# projekt.net
KiCad netlist of a schematic drawn in EAGLE
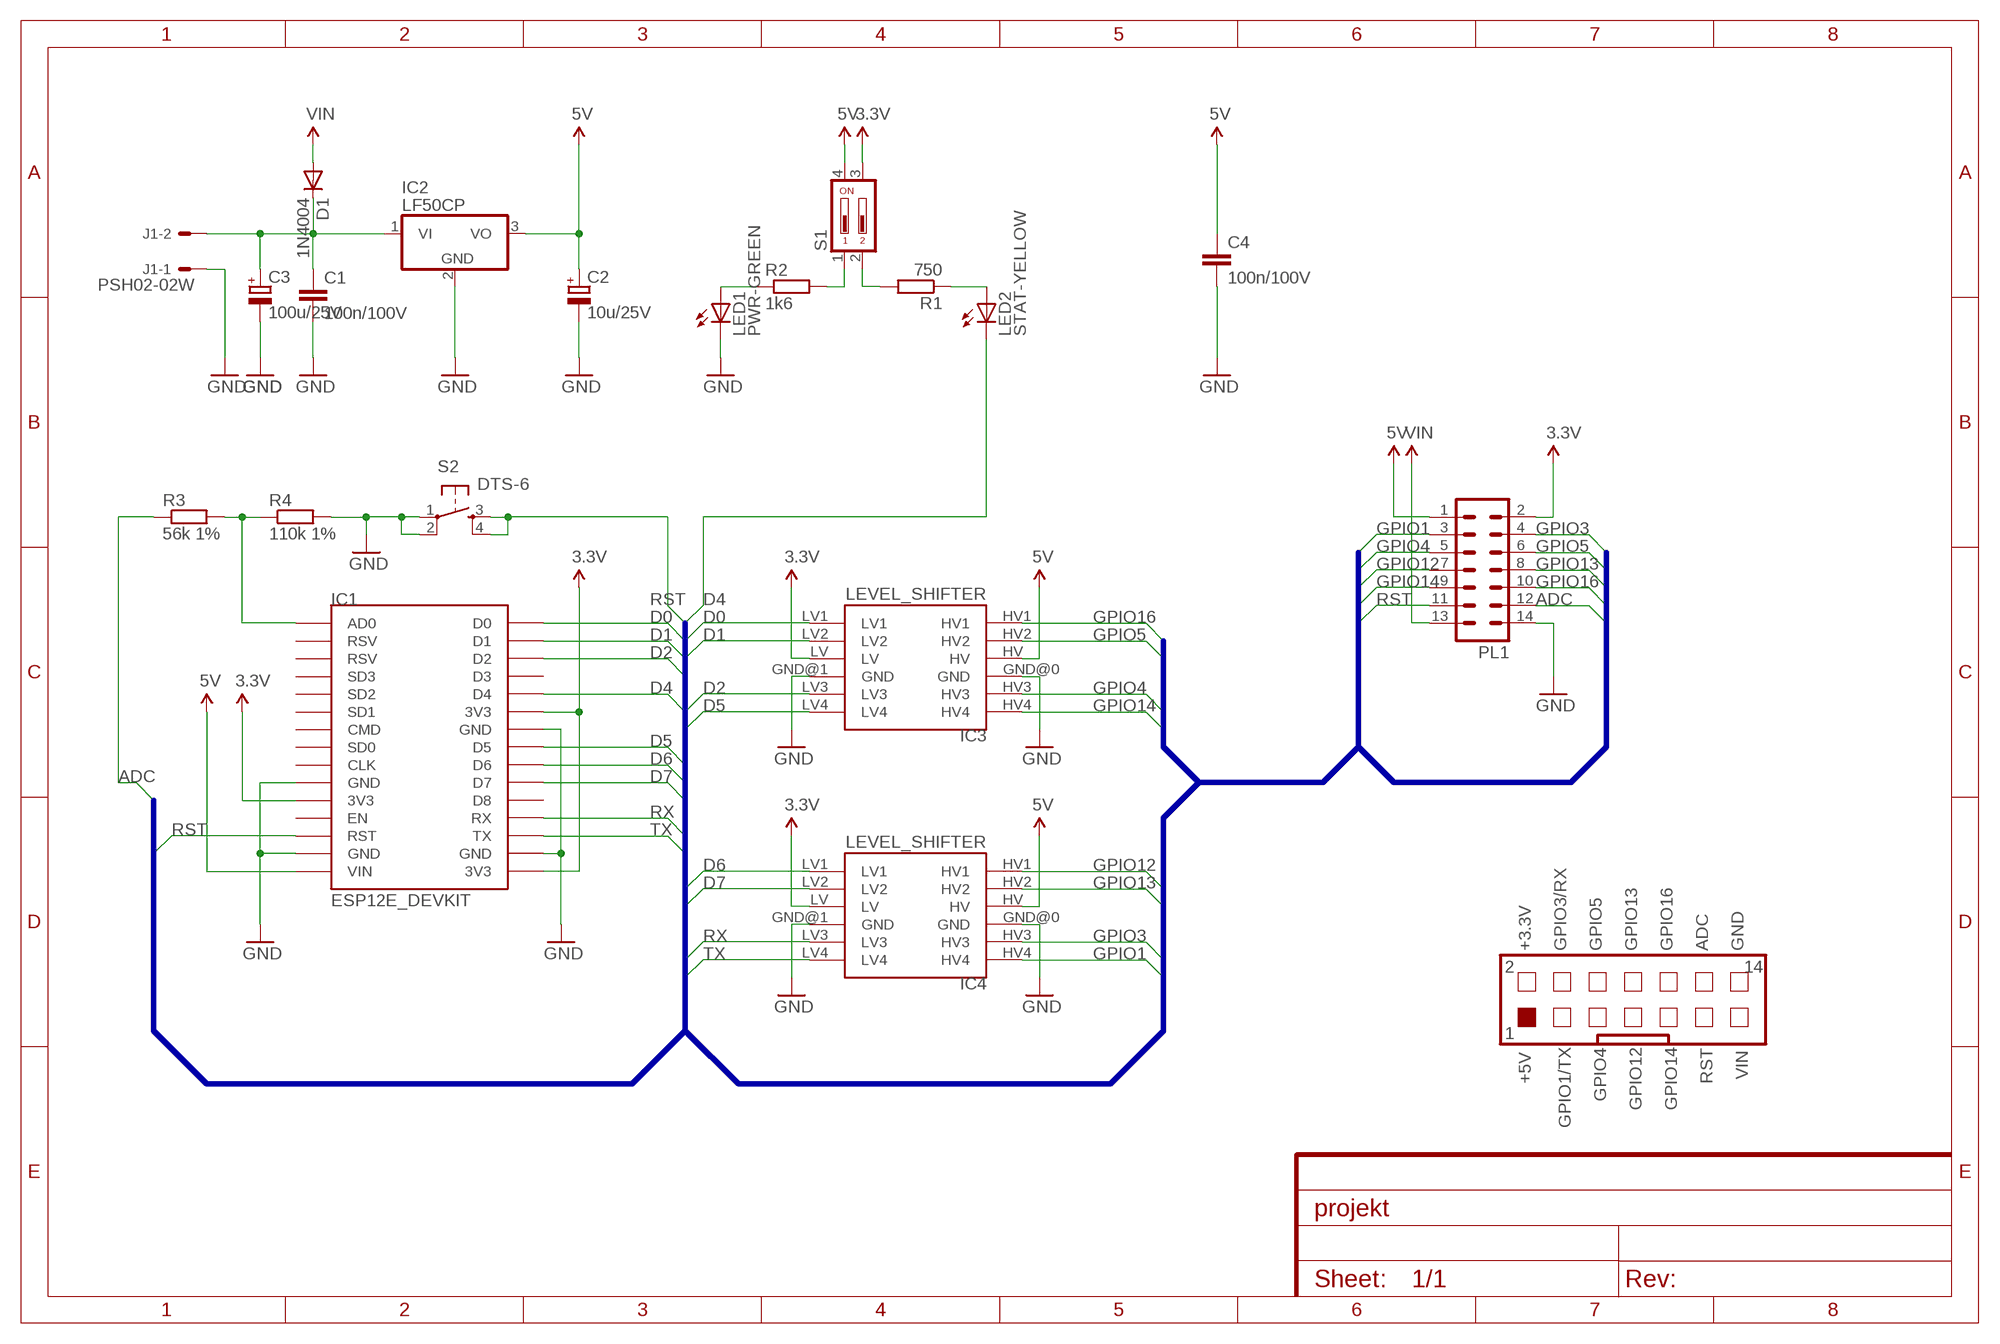
[diagram p0: schematic, sheet 1]

(export (version "E")
  (design (tool "Eeschema 10.0.6"))
  (components
    (comp (ref "C1")
      (value "100n/100V")
      (footprint "eagle-import:C025-025X050")
      (libsource (lib "eagle-import") (part "C-EUC025-025X050"))
    )
    (comp (ref "C2")
      (value "10u/25V")
      (footprint "eagle-import:E3,5-8")
      (libsource (lib "eagle-import") (part "CPOL-EUE3,5-8"))
    )
    (comp (ref "C3")
      (value "100u/25V")
      (footprint "eagle-import:E5-13")
      (libsource (lib "eagle-import") (part "CPOL-EUE5-13"))
    )
    (comp (ref "C4")
      (value "100n/100V")
      (footprint "eagle-import:C025-025X050")
      (libsource (lib "eagle-import") (part "C-EUC025-025X050"))
    )
    (comp (ref "D1")
      (value "1N4004")
      (footprint "eagle-import:DO41-10")
      (libsource (lib "eagle-import") (part "1N4004"))
    )
    (comp (ref "IC1")
      (value "ESP12E_DEVKIT")
      (footprint "eagle-import:ESP12E_DEVKIT")
      (libsource (lib "eagle-import") (part "ESP12E_DEVKIT"))
    )
    (comp (ref "IC2")
      (value "LF50CP")
      (footprint "eagle-import:TO220H")
      (libsource (lib "eagle-import") (part "LF50CP"))
    )
    (comp (ref "IC3")
      (value "LEVEL_SHIFTER")
      (footprint "eagle-import:LEVEL_SHIFTER")
      (libsource (lib "eagle-import") (part "LEVEL_SHIFTER"))
    )
    (comp (ref "IC4")
      (value "LEVEL_SHIFTER")
      (footprint "eagle-import:LEVEL_SHIFTER")
      (libsource (lib "eagle-import") (part "LEVEL_SHIFTER"))
    )
    (comp (ref "J1")
      (value "PSH02-02W")
      (footprint "eagle-import:7395-02")
      (libsource (lib "eagle-import") (part "22-?-0205-7028"))
    )
    (comp (ref "LED1")
      (value "PWR-GREEN")
      (footprint "eagle-import:LED3MM")
      (libsource (lib "eagle-import") (part "LED3MM"))
    )
    (comp (ref "LED2")
      (value "STAT-YELLOW")
      (footprint "eagle-import:LED3MM")
      (libsource (lib "eagle-import") (part "LED3MM"))
    )
    (comp (ref "PL1")
      (value "14H")
      (footprint "eagle-import:14H")
      (libsource (lib "eagle-import") (part "14H"))
    )
    (comp (ref "R1")
      (value "750")
      (footprint "eagle-import:R1206")
      (libsource (lib "eagle-import") (part "R-EU_R1206"))
    )
    (comp (ref "R2")
      (value "1k6")
      (footprint "eagle-import:R1206")
      (libsource (lib "eagle-import") (part "R-EU_R1206"))
    )
    (comp (ref "R3")
      (value "56k 1%")
      (footprint "eagle-import:R1206")
      (libsource (lib "eagle-import") (part "R-EU_R1206"))
    )
    (comp (ref "R4")
      (value "110k 1%")
      (footprint "eagle-import:R1206")
      (libsource (lib "eagle-import") (part "R-EU_R1206"))
    )
    (comp (ref "S1")
      (value "DIP02YL")
      (footprint "eagle-import:DIP02YL")
      (libsource (lib "eagle-import") (part "DIP02YL"))
    )
    (comp (ref "S2")
      (value "DTS-6")
      (footprint "eagle-import:DTS-6")
      (libsource (lib "eagle-import") (part "DTS-6"))
    )
  )
  (nets
    (net (code "1") (name "/ADC") (class "Default")
      (node (ref "PL1") (pin "12") (pinfunction "12_12") (pintype "passive"))
      (node (ref "R3") (pin "1") (pinfunction "1_1") (pintype "passive"))
    )
    (net (code "2") (name "/D0") (class "Default")
      (node (ref "IC1") (pin "D0") (pinfunction "D0_D0") (pintype "bidirectional"))
      (node (ref "IC3") (pin "LV1") (pinfunction "LV1_LV1") (pintype "bidirectional"))
    )
    (net (code "3") (name "/D1") (class "Default")
      (node (ref "IC1") (pin "D1") (pinfunction "D1_D1") (pintype "bidirectional"))
      (node (ref "IC3") (pin "LV2") (pinfunction "LV2_LV2") (pintype "bidirectional"))
    )
    (net (code "4") (name "/D2") (class "Default")
      (node (ref "IC1") (pin "D2") (pinfunction "D2_D2") (pintype "bidirectional"))
      (node (ref "IC3") (pin "LV3") (pinfunction "LV3_LV3") (pintype "bidirectional"))
    )
    (net (code "5") (name "/D4") (class "Default")
      (node (ref "IC1") (pin "D4") (pinfunction "D4_D4") (pintype "bidirectional"))
      (node (ref "LED2") (pin "K") (pinfunction "C_K") (pintype "passive"))
    )
    (net (code "6") (name "/D5") (class "Default")
      (node (ref "IC1") (pin "D5") (pinfunction "D5_D5") (pintype "bidirectional"))
      (node (ref "IC3") (pin "LV4") (pinfunction "LV4_LV4") (pintype "bidirectional"))
    )
    (net (code "7") (name "/D6") (class "Default")
      (node (ref "IC1") (pin "D6") (pinfunction "D6_D6") (pintype "bidirectional"))
      (node (ref "IC4") (pin "LV1") (pinfunction "LV1_LV1") (pintype "bidirectional"))
    )
    (net (code "8") (name "/D7") (class "Default")
      (node (ref "IC1") (pin "D7") (pinfunction "D7_D7") (pintype "bidirectional"))
      (node (ref "IC4") (pin "LV2") (pinfunction "LV2_LV2") (pintype "bidirectional"))
    )
    (net (code "9") (name "/GPIO1") (class "Default")
      (node (ref "IC4") (pin "HV4") (pinfunction "HV4_HV4") (pintype "bidirectional"))
      (node (ref "PL1") (pin "3") (pinfunction "3_3") (pintype "passive"))
    )
    (net (code "10") (name "/GPIO3") (class "Default")
      (node (ref "IC4") (pin "HV3") (pinfunction "HV3_HV3") (pintype "bidirectional"))
      (node (ref "PL1") (pin "4") (pinfunction "4_4") (pintype "passive"))
    )
    (net (code "11") (name "/GPIO4") (class "Default")
      (node (ref "IC3") (pin "HV3") (pinfunction "HV3_HV3") (pintype "bidirectional"))
      (node (ref "PL1") (pin "5") (pinfunction "5_5") (pintype "passive"))
    )
    (net (code "12") (name "/GPIO5") (class "Default")
      (node (ref "IC3") (pin "HV2") (pinfunction "HV2_HV2") (pintype "bidirectional"))
      (node (ref "PL1") (pin "6") (pinfunction "6_6") (pintype "passive"))
    )
    (net (code "13") (name "/GPIO12") (class "Default")
      (node (ref "IC4") (pin "HV1") (pinfunction "HV1_HV1") (pintype "bidirectional"))
      (node (ref "PL1") (pin "7") (pinfunction "7_7") (pintype "passive"))
    )
    (net (code "14") (name "/GPIO13") (class "Default")
      (node (ref "IC4") (pin "HV2") (pinfunction "HV2_HV2") (pintype "bidirectional"))
      (node (ref "PL1") (pin "8") (pinfunction "8_8") (pintype "passive"))
    )
    (net (code "15") (name "/GPIO14") (class "Default")
      (node (ref "IC3") (pin "HV4") (pinfunction "HV4_HV4") (pintype "bidirectional"))
      (node (ref "PL1") (pin "9") (pinfunction "9_9") (pintype "passive"))
    )
    (net (code "16") (name "/GPIO16") (class "Default")
      (node (ref "IC3") (pin "HV1") (pinfunction "HV1_HV1") (pintype "bidirectional"))
      (node (ref "PL1") (pin "10") (pinfunction "10_10") (pintype "passive"))
    )
    (net (code "17") (name "/RST") (class "Default")
      (node (ref "IC1") (pin "RST") (pinfunction "RST_RST") (pintype "bidirectional"))
      (node (ref "PL1") (pin "11") (pinfunction "11_11") (pintype "passive"))
      (node (ref "S2") (pin "3") (pinfunction "3_3") (pintype "passive"))
      (node (ref "S2") (pin "4") (pinfunction "4_4") (pintype "passive"))
    )
    (net (code "18") (name "/RX") (class "Default")
      (node (ref "IC1") (pin "RX") (pinfunction "RX_RX") (pintype "bidirectional"))
      (node (ref "IC4") (pin "LV3") (pinfunction "LV3_LV3") (pintype "bidirectional"))
    )
    (net (code "19") (name "/TX") (class "Default")
      (node (ref "IC1") (pin "TX") (pinfunction "TX_TX") (pintype "bidirectional"))
      (node (ref "IC4") (pin "LV4") (pinfunction "LV4_LV4") (pintype "bidirectional"))
    )
    (net (code "20") (name "3.3V") (class "Default")
      (node (ref "IC1") (pin "3V3@0") (pinfunction "3V3_3V3@0") (pintype "bidirectional"))
      (node (ref "IC1") (pin "3V3@1") (pinfunction "3V3_3V3@1") (pintype "bidirectional"))
      (node (ref "IC1") (pin "3V3@2") (pinfunction "3V3_3V3@2") (pintype "bidirectional"))
      (node (ref "IC3") (pin "LV") (pinfunction "LV_LV") (pintype "bidirectional"))
      (node (ref "IC4") (pin "LV") (pinfunction "LV_LV") (pintype "bidirectional"))
      (node (ref "PL1") (pin "2") (pinfunction "2_2") (pintype "passive"))
      (node (ref "S1") (pin "3") (pinfunction "3_3") (pintype "passive"))
    )
    (net (code "21") (name "5V") (class "Default")
      (node (ref "C2") (pin "+") (pinfunction "+_+") (pintype "passive"))
      (node (ref "C4") (pin "1") (pinfunction "1_1") (pintype "passive"))
      (node (ref "IC1") (pin "VIN") (pinfunction "VIN_VIN") (pintype "bidirectional"))
      (node (ref "IC2") (pin "3") (pinfunction "VO_3") (pintype "passive"))
      (node (ref "IC3") (pin "HV") (pinfunction "HV_HV") (pintype "bidirectional"))
      (node (ref "IC4") (pin "HV") (pinfunction "HV_HV") (pintype "bidirectional"))
      (node (ref "PL1") (pin "1") (pinfunction "1_1") (pintype "passive"))
      (node (ref "S1") (pin "4") (pinfunction "4_4") (pintype "passive"))
    )
    (net (code "22") (name "GND") (class "Default")
      (node (ref "C1") (pin "2") (pinfunction "2_2") (pintype "passive"))
      (node (ref "C2") (pin "-") (pinfunction "-_-") (pintype "passive"))
      (node (ref "C3") (pin "-") (pinfunction "-_-") (pintype "passive"))
      (node (ref "C4") (pin "2") (pinfunction "2_2") (pintype "passive"))
      (node (ref "IC1") (pin "GND@0") (pinfunction "GND_GND@0") (pintype "bidirectional"))
      (node (ref "IC1") (pin "GND@1") (pinfunction "GND_GND@1") (pintype "bidirectional"))
      (node (ref "IC1") (pin "GND@2") (pinfunction "GND_GND@2") (pintype "bidirectional"))
      (node (ref "IC1") (pin "GND@3") (pinfunction "GND_GND@3") (pintype "bidirectional"))
      (node (ref "IC2") (pin "2") (pinfunction "GND_2") (pintype "passive"))
      (node (ref "IC3") (pin "GND@0") (pinfunction "GND_GND@0") (pintype "bidirectional"))
      (node (ref "IC3") (pin "GND@1") (pinfunction "GND_GND@1") (pintype "bidirectional"))
      (node (ref "IC4") (pin "GND@0") (pinfunction "GND_GND@0") (pintype "bidirectional"))
      (node (ref "IC4") (pin "GND@1") (pinfunction "GND_GND@1") (pintype "bidirectional"))
      (node (ref "J1") (pin "1") (pinfunction "S_1") (pintype "passive"))
      (node (ref "LED1") (pin "K") (pinfunction "C_K") (pintype "passive"))
      (node (ref "PL1") (pin "14") (pinfunction "14_14") (pintype "passive"))
      (node (ref "R4") (pin "2") (pinfunction "2_2") (pintype "passive"))
      (node (ref "S2") (pin "1") (pinfunction "1_1") (pintype "passive"))
      (node (ref "S2") (pin "2") (pinfunction "2_2") (pintype "passive"))
    )
    (net (code "23") (name "Net-(IC1-PadAD0)") (class "Default")
      (node (ref "IC1") (pin "AD0") (pinfunction "AD0_AD0") (pintype "bidirectional"))
      (node (ref "R3") (pin "2") (pinfunction "2_2") (pintype "passive"))
      (node (ref "R4") (pin "1") (pinfunction "1_1") (pintype "passive"))
    )
    (net (code "24") (name "Net-(IC2-VI)") (class "Default")
      (node (ref "C1") (pin "1") (pinfunction "1_1") (pintype "passive"))
      (node (ref "C3") (pin "+") (pinfunction "+_+") (pintype "passive"))
      (node (ref "D1") (pin "C") (pinfunction "C_C") (pintype "passive"))
      (node (ref "IC2") (pin "1") (pinfunction "VI_1") (pintype "input"))
      (node (ref "J1") (pin "2") (pinfunction "S_2") (pintype "passive"))
    )
    (net (code "25") (name "Net-(LED1-PadA)") (class "Default")
      (node (ref "LED1") (pin "A") (pinfunction "A_A") (pintype "passive"))
      (node (ref "R2") (pin "1") (pinfunction "1_1") (pintype "passive"))
    )
    (net (code "26") (name "Net-(LED2-PadA)") (class "Default")
      (node (ref "LED2") (pin "A") (pinfunction "A_A") (pintype "passive"))
      (node (ref "R1") (pin "1") (pinfunction "1_1") (pintype "passive"))
    )
    (net (code "27") (name "Net-(R1-Pad2)") (class "Default")
      (node (ref "R1") (pin "2") (pinfunction "2_2") (pintype "passive"))
      (node (ref "S1") (pin "2") (pinfunction "2_2") (pintype "passive"))
    )
    (net (code "28") (name "Net-(R2-Pad2)") (class "Default")
      (node (ref "R2") (pin "2") (pinfunction "2_2") (pintype "passive"))
      (node (ref "S1") (pin "1") (pinfunction "1_1") (pintype "passive"))
    )
    (net (code "29") (name "VIN") (class "Default")
      (node (ref "D1") (pin "A") (pinfunction "A_A") (pintype "passive"))
      (node (ref "PL1") (pin "13") (pinfunction "13_13") (pintype "passive"))
    )
    (net (code "30") (name "unconnected-(IC1-PadCLK)") (class "Default")
      (node (ref "IC1") (pin "CLK") (pinfunction "CLK_CLK") (pintype "bidirectional"))
    )
    (net (code "31") (name "unconnected-(IC1-PadCMD)") (class "Default")
      (node (ref "IC1") (pin "CMD") (pinfunction "CMD_CMD") (pintype "bidirectional"))
    )
    (net (code "32") (name "unconnected-(IC1-PadD3)") (class "Default")
      (node (ref "IC1") (pin "D3") (pinfunction "D3_D3") (pintype "bidirectional"))
    )
    (net (code "33") (name "unconnected-(IC1-PadD8)") (class "Default")
      (node (ref "IC1") (pin "D8") (pinfunction "D8_D8") (pintype "bidirectional"))
    )
    (net (code "34") (name "unconnected-(IC1-PadEN)") (class "Default")
      (node (ref "IC1") (pin "EN") (pinfunction "EN_EN") (pintype "bidirectional"))
    )
    (net (code "35") (name "unconnected-(IC1-PadSD0)") (class "Default")
      (node (ref "IC1") (pin "SD0") (pinfunction "SD0_SD0") (pintype "bidirectional"))
    )
    (net (code "36") (name "unconnected-(IC1-PadSD1)") (class "Default")
      (node (ref "IC1") (pin "SD1") (pinfunction "SD1_SD1") (pintype "bidirectional"))
    )
    (net (code "37") (name "unconnected-(IC1-PadSD2)") (class "Default")
      (node (ref "IC1") (pin "SD2") (pinfunction "SD2_SD2") (pintype "bidirectional"))
    )
    (net (code "38") (name "unconnected-(IC1-PadSD3)") (class "Default")
      (node (ref "IC1") (pin "SD3") (pinfunction "SD3_SD3") (pintype "bidirectional"))
    )
    (net (code "39") (name "unconnected-(IC1-RSV-PadRSV@0)") (class "Default")
      (node (ref "IC1") (pin "RSV@0") (pinfunction "RSV_RSV@0") (pintype "bidirectional"))
    )
    (net (code "40") (name "unconnected-(IC1-RSV-PadRSV@1)") (class "Default")
      (node (ref "IC1") (pin "RSV@1") (pinfunction "RSV_RSV@1") (pintype "bidirectional"))
    )
  )
)
